# CAN_Breakout.net
KiCad netlist of a schematic drawn in Altium Designer
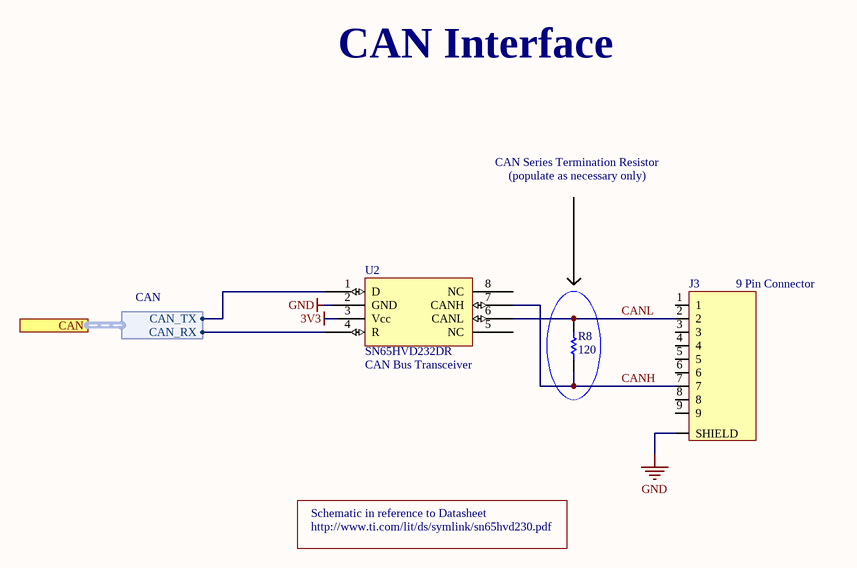
[diagram p0: CAN_Breakout.SchDoc]

(export (version "E")
  (design (tool "Eeschema 10.0.6"))
  (components
    (comp (ref "J3")
      (value "9 Pin Connector")
      (footprint "LaunchyRIOFootprints:9-Pos D-Sub")
      (description "9-Position Connector")
      (libsource (lib "LaunchyRIOComponents") (part "9-Position Connector"))
    )
    (comp (ref "R8")
      (value "120")
      (footprint "0402")
      (description "Resistor")
      (fields (field (name "Comment") "Res1"))
      (libsource (lib "Miscellaneous Devices") (part "Res1"))
    )
    (comp (ref "U2")
      (value "CAN Bus Transceiver")
      (footprint "8SOIC-CAN-TRANSCEIVER")
      (fields
        (field (name "MANUFACTURER") "Texas Instruments")
        (field (name "MANUFACTURER PART NUMBER") "SN65HVD232DR")
        (field (name "DIGIKEY PART NUMBER") "296-26344-1-ND")
      )
      (libsource (lib "LaunchyRIOComponents") (part "SN65HVD232DR"))
    )
  )
  (nets
    (net (code "2") (name "/CANH") (class "Default")
      (node (ref "J3") (pin "7") (pinfunction "7_7") (pintype "bidirectional"))
      (node (ref "R8") (pin "1") (pinfunction "1_1") (pintype "passive"))
      (node (ref "U2") (pin "7") (pinfunction "CANH_7") (pintype "bidirectional"))
    )
    (net (code "3") (name "/CANL") (class "Default")
      (node (ref "J3") (pin "2") (pinfunction "2_2") (pintype "bidirectional"))
      (node (ref "R8") (pin "2") (pinfunction "2_2") (pintype "passive"))
      (node (ref "U2") (pin "6") (pinfunction "CANL_6") (pintype "bidirectional"))
    )
    (net (code "4") (name "/CAN_RX") (class "Default")
      (node (ref "U2") (pin "4") (pinfunction "R_4") (pintype "bidirectional"))
    )
    (net (code "5") (name "/CAN_TX") (class "Default")
      (node (ref "U2") (pin "1") (pinfunction "D_1") (pintype "bidirectional"))
    )
    (net (code "7") (name "3V3") (class "Default")
      (node (ref "U2") (pin "3") (pinfunction "Vcc_3") (pintype "power_in"))
    )
    (net (code "8") (name "GND") (class "Default")
      (node (ref "J3") (pin "SHIELD") (pinfunction "SHIELD_SHIELD") (pintype "passive"))
      (node (ref "U2") (pin "2") (pinfunction "GND_2") (pintype "power_in"))
    )
    (net (code "9") (name "unconnected-(J3-Pad1)") (class "Default")
      (node (ref "J3") (pin "1") (pinfunction "1_1") (pintype "bidirectional"))
    )
    (net (code "10") (name "unconnected-(J3-Pad3)") (class "Default")
      (node (ref "J3") (pin "3") (pinfunction "3_3") (pintype "bidirectional"))
    )
    (net (code "11") (name "unconnected-(J3-Pad4)") (class "Default")
      (node (ref "J3") (pin "4") (pinfunction "4_4") (pintype "bidirectional"))
    )
    (net (code "12") (name "unconnected-(J3-Pad5)") (class "Default")
      (node (ref "J3") (pin "5") (pinfunction "5_5") (pintype "bidirectional"))
    )
    (net (code "13") (name "unconnected-(J3-Pad6)") (class "Default")
      (node (ref "J3") (pin "6") (pinfunction "6_6") (pintype "bidirectional"))
    )
    (net (code "14") (name "unconnected-(J3-Pad8)") (class "Default")
      (node (ref "J3") (pin "8") (pinfunction "8_8") (pintype "bidirectional"))
    )
    (net (code "15") (name "unconnected-(J3-Pad9)") (class "Default")
      (node (ref "J3") (pin "9") (pinfunction "9_9") (pintype "bidirectional"))
    )
    (net (code "16") (name "unconnected-(U2-NC-Pad5)") (class "Default")
      (node (ref "U2") (pin "5") (pinfunction "NC_5") (pintype "passive"))
    )
    (net (code "17") (name "unconnected-(U2-NC-Pad8)") (class "Default")
      (node (ref "U2") (pin "8") (pinfunction "NC_8") (pintype "passive"))
    )
  )
)
